# Power-Final.net
KiCad netlist of a schematic drawn in EAGLE
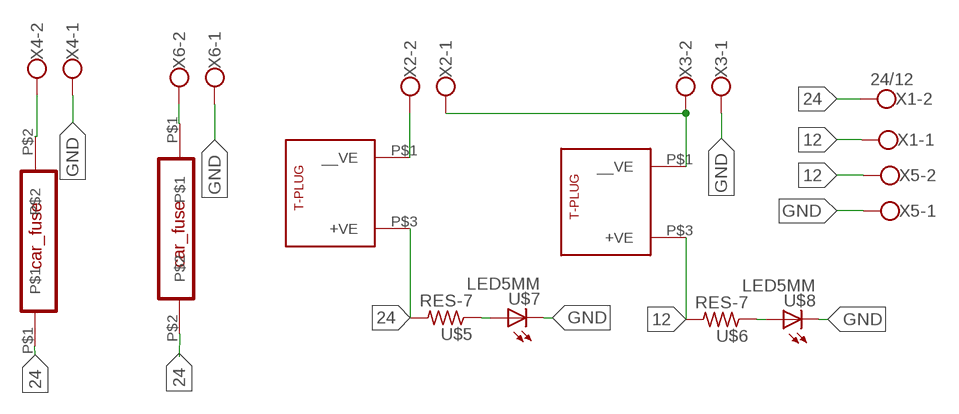
[diagram p0: schematic, sheet 1]

(export (version "E")
  (design (tool "Eeschema 10.0.6"))
  (components
    (comp (ref "U$1")
      (value "CAR_FUSE")
      (footprint "eagle-import:CAR_FUSE")
      (libsource (lib "eagle-import") (part "CAR_FUSE"))
    )
    (comp (ref "U$2")
      (value "CAR_FUSE")
      (footprint "eagle-import:CAR_FUSE")
      (libsource (lib "eagle-import") (part "CAR_FUSE"))
    )
    (comp (ref "U$3")
      (value "T_CONNECTOR")
      (footprint "eagle-import:T-PLUG")
      (libsource (lib "eagle-import") (part "T_CONNECTOR"))
    )
    (comp (ref "U$4")
      (value "T_CONNECTOR")
      (footprint "eagle-import:T-PLUG")
      (libsource (lib "eagle-import") (part "T_CONNECTOR"))
    )
    (comp (ref "U$5")
      (value "RES-7")
      (footprint "eagle-import:0204_7")
      (libsource (lib "eagle-import") (part "RES-7"))
    )
    (comp (ref "U$6")
      (value "RES-7")
      (footprint "eagle-import:0204_7")
      (libsource (lib "eagle-import") (part "RES-7"))
    )
    (comp (ref "U$7")
      (value "LED5MM")
      (footprint "eagle-import:LED5MM")
      (libsource (lib "eagle-import") (part "LED5MM"))
    )
    (comp (ref "U$8")
      (value "LED5MM")
      (footprint "eagle-import:LED5MM")
      (libsource (lib "eagle-import") (part "LED5MM"))
    )
    (comp (ref "X1")
      (value "24/12")
      (footprint "eagle-import:W239-302")
      (libsource (lib "eagle-import") (part "ROSTA.POWER"))
    )
    (comp (ref "X2")
      (value "ROSTA.POWER")
      (footprint "eagle-import:W239-302")
      (libsource (lib "eagle-import") (part "ROSTA.POWER"))
    )
    (comp (ref "X3")
      (value "ROSTA.POWER")
      (footprint "eagle-import:W239-302")
      (libsource (lib "eagle-import") (part "ROSTA.POWER"))
    )
    (comp (ref "X4")
      (value "ROSTA.POWER")
      (footprint "eagle-import:W239-302")
      (libsource (lib "eagle-import") (part "ROSTA.POWER"))
    )
    (comp (ref "X5")
      (value "ROSTA.POWER")
      (footprint "eagle-import:W239-302")
      (libsource (lib "eagle-import") (part "ROSTA.POWER"))
    )
    (comp (ref "X6")
      (value "ROSTA.POWER")
      (footprint "eagle-import:W239-302")
      (libsource (lib "eagle-import") (part "ROSTA.POWER"))
    )
  )
  (nets
    (net (code "1") (name "12") (class "Default")
      (node (ref "U$4") (pin "P$3") (pinfunction "+VE_P$3") (pintype "bidirectional"))
      (node (ref "U$6") (pin "2") (pinfunction "2_2") (pintype "passive"))
      (node (ref "X1") (pin "1") (pinfunction "KL_1") (pintype "passive"))
      (node (ref "X5") (pin "2") (pinfunction "KL_2") (pintype "passive"))
    )
    (net (code "2") (name "24") (class "Default")
      (node (ref "U$1") (pin "P$1") (pinfunction "P$1_P$1") (pintype "bidirectional"))
      (node (ref "U$2") (pin "P$2") (pinfunction "P$2_P$2") (pintype "bidirectional"))
      (node (ref "U$3") (pin "P$3") (pinfunction "+VE_P$3") (pintype "bidirectional"))
      (node (ref "U$5") (pin "2") (pinfunction "2_2") (pintype "passive"))
      (node (ref "X1") (pin "2") (pinfunction "KL_2") (pintype "passive"))
    )
    (net (code "3") (name "GND") (class "Default")
      (node (ref "U$7") (pin "K") (pinfunction "C_K") (pintype "passive"))
      (node (ref "U$8") (pin "K") (pinfunction "C_K") (pintype "passive"))
      (node (ref "X3") (pin "1") (pinfunction "KL_1") (pintype "passive"))
      (node (ref "X4") (pin "1") (pinfunction "KL_1") (pintype "passive"))
      (node (ref "X5") (pin "1") (pinfunction "KL_1") (pintype "passive"))
      (node (ref "X6") (pin "1") (pinfunction "KL_1") (pintype "passive"))
    )
    (net (code "4") (name "Net-(U$3-__VE)") (class "Default")
      (node (ref "U$3") (pin "P$1") (pinfunction "__VE_P$1") (pintype "bidirectional"))
      (node (ref "X2") (pin "2") (pinfunction "KL_2") (pintype "passive"))
    )
    (net (code "5") (name "Net-(U$4-__VE)") (class "Default")
      (node (ref "U$4") (pin "P$1") (pinfunction "__VE_P$1") (pintype "bidirectional"))
      (node (ref "X2") (pin "1") (pinfunction "KL_1") (pintype "passive"))
      (node (ref "X3") (pin "2") (pinfunction "KL_2") (pintype "passive"))
    )
    (net (code "6") (name "Net-(U$5-Pad1)") (class "Default")
      (node (ref "U$5") (pin "1") (pinfunction "1_1") (pintype "passive"))
      (node (ref "U$7") (pin "A") (pinfunction "A_A") (pintype "passive"))
    )
    (net (code "7") (name "Net-(U$6-Pad1)") (class "Default")
      (node (ref "U$6") (pin "1") (pinfunction "1_1") (pintype "passive"))
      (node (ref "U$8") (pin "A") (pinfunction "A_A") (pintype "passive"))
    )
    (net (code "8") (name "Net-(X4B-KL)") (class "Default")
      (node (ref "U$1") (pin "P$2") (pinfunction "P$2_P$2") (pintype "bidirectional"))
      (node (ref "X4") (pin "2") (pinfunction "KL_2") (pintype "passive"))
    )
    (net (code "9") (name "Net-(X6B-KL)") (class "Default")
      (node (ref "U$2") (pin "P$1") (pinfunction "P$1_P$1") (pintype "bidirectional"))
      (node (ref "X6") (pin "2") (pinfunction "KL_2") (pintype "passive"))
    )
  )
)
